# simple-buffer-with-jacks-V0-3.net
KiCad netlist of a schematic drawn in EAGLE
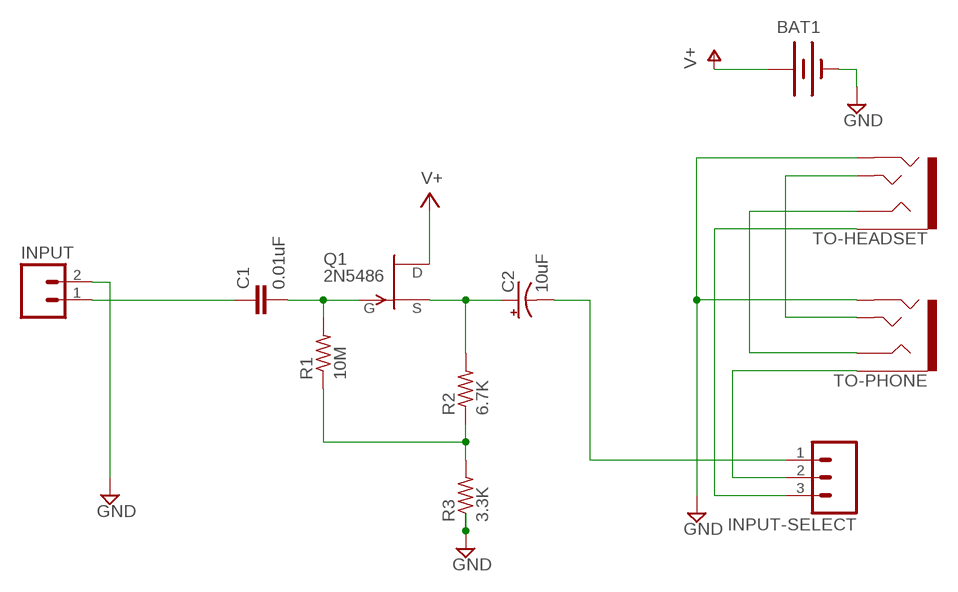
[diagram p0: schematic, sheet 1]

(export (version "E")
  (design (tool "Eeschema 10.0.6"))
  (components
    (comp (ref "BAT1")
      (value "BATTERYAAA-KIT")
      (footprint "eagle-import:BATTERY-AAA-KIT")
      (libsource (lib "eagle-import") (part "BATTERYAAA-KIT"))
    )
    (comp (ref "C1")
      (value "0.01uF")
      (footprint "eagle-import:C5B3")
      (libsource (lib "eagle-import") (part "C5/3"))
    )
    (comp (ref "C2")
      (value "10uF")
      (footprint "eagle-import:CPOL-RADIAL-10UF-25V")
      (libsource (lib "eagle-import") (part "CAP_POLPTH2"))
    )
    (comp (ref "INPUT")
      (value "M02LOCK")
      (footprint "eagle-import:1X02_LOCK")
      (libsource (lib "eagle-import") (part "M02LOCK"))
    )
    (comp (ref "INPUT-SELECT")
      (value "M03LOCK")
      (footprint "eagle-import:1X03_LOCK")
      (libsource (lib "eagle-import") (part "M03LOCK"))
    )
    (comp (ref "Q1")
      (value "2N5486")
      (footprint "eagle-import:TO92-")
      (libsource (lib "eagle-import") (part "?5482N6"))
    )
    (comp (ref "R1")
      (value "10M")
      (footprint "eagle-import:V526-0")
      (libsource (lib "eagle-import") (part "R-US_V526-0"))
    )
    (comp (ref "R2")
      (value "6.7K")
      (footprint "eagle-import:V526-0")
      (libsource (lib "eagle-import") (part "R-US_V526-0"))
    )
    (comp (ref "R3")
      (value "3.3K")
      (footprint "eagle-import:V526-0")
      (libsource (lib "eagle-import") (part "R-US_V526-0"))
    )
    (comp (ref "TO-HEADSET")
      (value "AUDIO-JACK3")
      (footprint "eagle-import:AUDIO-JACK-TRRS-SMD")
      (libsource (lib "eagle-import") (part "AUDIO-JACK3"))
    )
    (comp (ref "TO-PHONE")
      (value "AUDIO-JACK3")
      (footprint "eagle-import:AUDIO-JACK-TRRS-SMD")
      (libsource (lib "eagle-import") (part "AUDIO-JACK3"))
    )
  )
  (nets
    (net (code "1") (name "GND") (class "Default")
      (node (ref "BAT1") (pin "GND@1") (pinfunction "-_GND@1") (pintype "power_in"))
      (node (ref "INPUT") (pin "2") (pinfunction "2_2") (pintype "passive"))
      (node (ref "R3") (pin "1") (pinfunction "1_1") (pintype "passive"))
      (node (ref "TO-HEADSET") (pin "RING2") (pinfunction "RING2_RING2") (pintype "bidirectional"))
      (node (ref "TO-PHONE") (pin "RING2") (pinfunction "RING2_RING2") (pintype "bidirectional"))
    )
    (net (code "2") (name "Net-(C1-Pad1)") (class "Default")
      (node (ref "C1") (pin "1") (pinfunction "1_1") (pintype "passive"))
      (node (ref "INPUT") (pin "1") (pinfunction "1_1") (pintype "passive"))
    )
    (net (code "3") (name "Net-(C2-+)") (class "Default")
      (node (ref "C2") (pin "1") (pinfunction "+_1") (pintype "passive"))
      (node (ref "Q1") (pin "2") (pinfunction "S_2") (pintype "passive"))
      (node (ref "R2") (pin "2") (pinfunction "2_2") (pintype "passive"))
    )
    (net (code "4") (name "Net-(C2--)") (class "Default")
      (node (ref "C2") (pin "2") (pinfunction "-_2") (pintype "passive"))
      (node (ref "INPUT-SELECT") (pin "1") (pinfunction "1_1") (pintype "passive"))
    )
    (net (code "5") (name "Net-(INPUT-SELECT-Pad2)") (class "Default")
      (node (ref "INPUT-SELECT") (pin "2") (pinfunction "2_2") (pintype "passive"))
      (node (ref "TO-PHONE") (pin "EARTH") (pinfunction "EARTH_EARTH") (pintype "bidirectional"))
    )
    (net (code "6") (name "Net-(INPUT-SELECT-Pad3)") (class "Default")
      (node (ref "INPUT-SELECT") (pin "3") (pinfunction "3_3") (pintype "passive"))
      (node (ref "TO-HEADSET") (pin "EARTH") (pinfunction "EARTH_EARTH") (pintype "bidirectional"))
    )
    (net (code "7") (name "Net-(Q1-G)") (class "Default")
      (node (ref "C1") (pin "2") (pinfunction "2_2") (pintype "passive"))
      (node (ref "Q1") (pin "1") (pinfunction "G_1") (pintype "passive"))
      (node (ref "R1") (pin "2") (pinfunction "2_2") (pintype "passive"))
    )
    (net (code "8") (name "Net-(R1-Pad1)") (class "Default")
      (node (ref "R1") (pin "1") (pinfunction "1_1") (pintype "passive"))
      (node (ref "R2") (pin "1") (pinfunction "1_1") (pintype "passive"))
      (node (ref "R3") (pin "2") (pinfunction "2_2") (pintype "passive"))
    )
    (net (code "9") (name "Net-(TO-HEADSET-PadRING1)") (class "Default")
      (node (ref "TO-HEADSET") (pin "RING1") (pinfunction "RING1_RING1") (pintype "bidirectional"))
      (node (ref "TO-PHONE") (pin "RING1") (pinfunction "RING1_RING1") (pintype "bidirectional"))
    )
    (net (code "10") (name "Net-(TO-HEADSET-PadTIP)") (class "Default")
      (node (ref "TO-HEADSET") (pin "TIP") (pinfunction "TIP_TIP") (pintype "bidirectional"))
      (node (ref "TO-PHONE") (pin "TIP") (pinfunction "TIP_TIP") (pintype "bidirectional"))
    )
    (net (code "11") (name "V+") (class "Default")
      (node (ref "BAT1") (pin "PWR@1") (pinfunction "+_PWR@1") (pintype "power_in"))
      (node (ref "Q1") (pin "3") (pinfunction "D_3") (pintype "passive"))
    )
  )
)
